# SmartSwitch_i2c.net
KiCad netlist of a schematic drawn in EAGLE
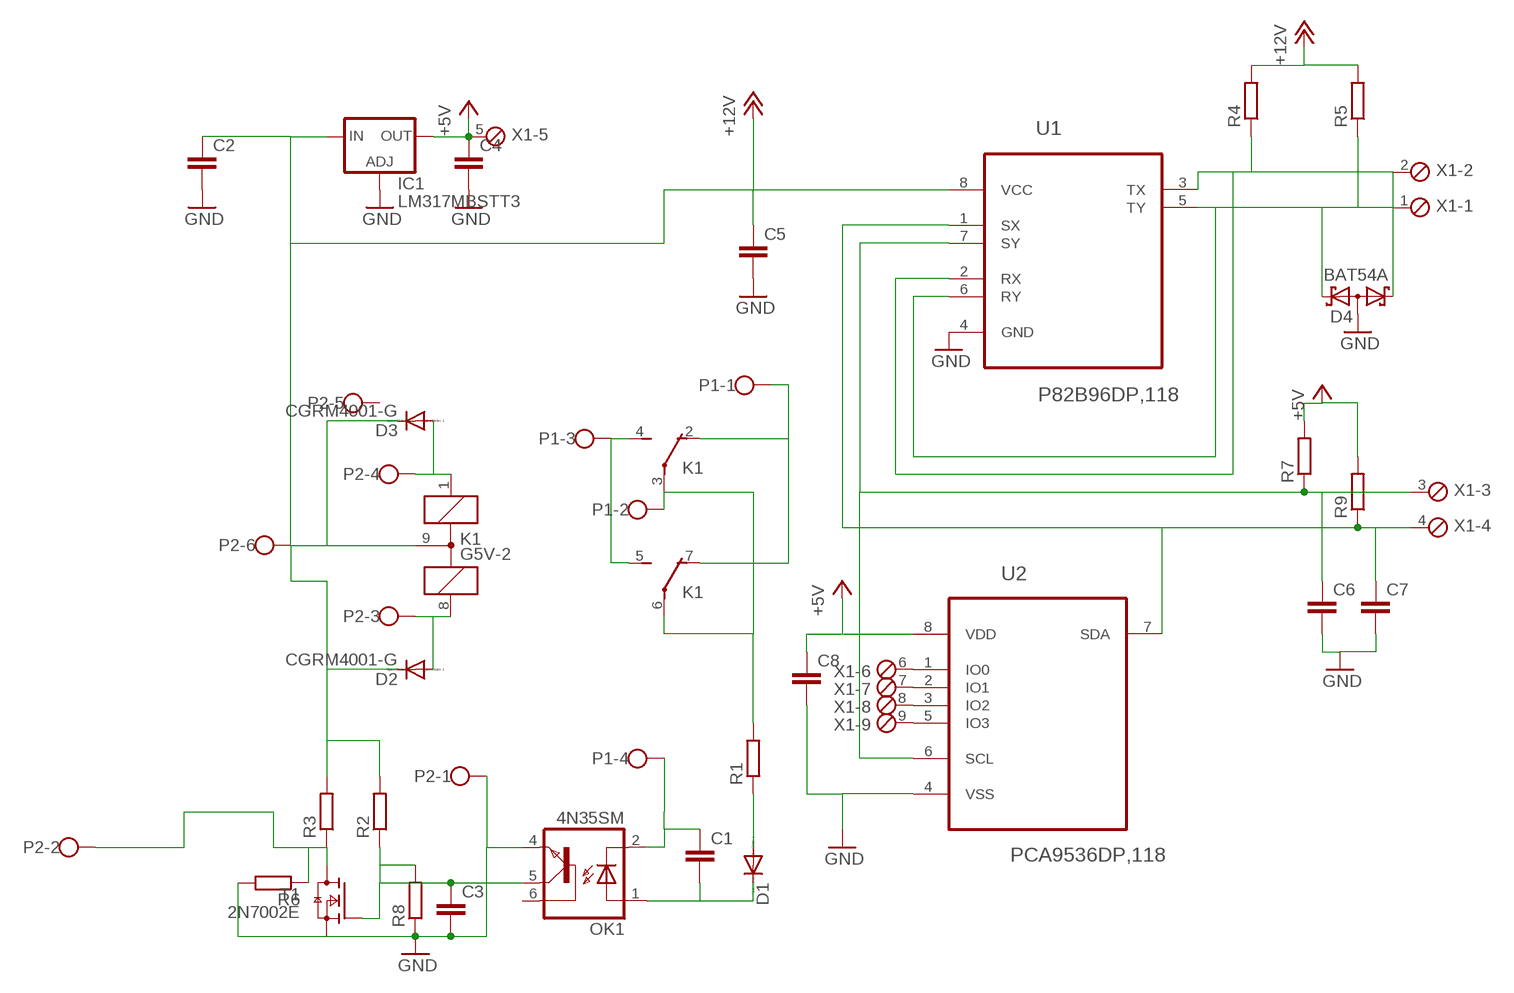
[diagram p0: schematic, sheet 1]

(export (version "E")
  (design (tool "Eeschema 10.0.6"))
  (components
    (comp (ref "C1")
      (value "C-EUC0805K")
      (footprint "eagle-import:C0805K")
      (libsource (lib "eagle-import") (part "resistor_C-EUC0805K"))
    )
    (comp (ref "C2")
      (value "C-EUC0805K")
      (footprint "eagle-import:C0805K")
      (libsource (lib "eagle-import") (part "resistor_C-EUC0805K"))
    )
    (comp (ref "C3")
      (value "C-EUC0805K")
      (footprint "eagle-import:C0805K")
      (libsource (lib "eagle-import") (part "resistor_C-EUC0805K"))
    )
    (comp (ref "C4")
      (value "C-EUC0805K")
      (footprint "eagle-import:C0805K")
      (libsource (lib "eagle-import") (part "resistor_C-EUC0805K"))
    )
    (comp (ref "C5")
      (value "C-EUC0603K")
      (footprint "eagle-import:C0603K")
      (libsource (lib "eagle-import") (part "C-EUC0603K"))
    )
    (comp (ref "C6")
      (value "C-EUC0402")
      (footprint "eagle-import:C0402")
      (libsource (lib "eagle-import") (part "C-EUC0402"))
    )
    (comp (ref "C7")
      (value "C-EUC0402")
      (footprint "eagle-import:C0402")
      (libsource (lib "eagle-import") (part "C-EUC0402"))
    )
    (comp (ref "C8")
      (value "C-EUC0603K")
      (footprint "eagle-import:C0603K")
      (libsource (lib "eagle-import") (part "C-EUC0603K"))
    )
    (comp (ref "D1")
      (value "DIODE-DO-214AC")
      (footprint "eagle-import:DO-214AC")
      (libsource (lib "eagle-import") (part "DIODE-DO-214AC"))
    )
    (comp (ref "D2")
      (value "CGRM4001-G")
      (footprint "eagle-import:SOD-123_MINI-SMA")
      (libsource (lib "eagle-import") (part "CGRM400-G1"))
    )
    (comp (ref "D3")
      (value "CGRM4001-G")
      (footprint "eagle-import:SOD-123_MINI-SMA")
      (libsource (lib "eagle-import") (part "CGRM400-G1"))
    )
    (comp (ref "D4")
      (value "BAT54A")
      (footprint "eagle-import:SOT23")
      (libsource (lib "eagle-import") (part "BAT54A"))
    )
    (comp (ref "IC1")
      (value "LM317MBSTT3")
      (footprint "eagle-import:SOT223")
      (libsource (lib "eagle-import") (part "LM317?MBSTT3"))
    )
    (comp (ref "K1")
      (value "G5V-2")
      (footprint "eagle-import:G5V-2")
      (fields (field (name "MPN") "G5V-2 5DC"))
      (libsource (lib "eagle-import") (part "G5V-2"))
    )
    (comp (ref "OK1")
      (value "4N35SM")
      (footprint "eagle-import:DIL6-SMD")
      (fields (field (name "MF") "FAIRCHILD SEMICONDUCTOR") (field (name "MPN") "4N35S-M"))
      (libsource (lib "eagle-import") (part "4N?MS35"))
    )
    (comp (ref "P1")
      (value "W237-4")
      (footprint "eagle-import:W237-4")
      (libsource (lib "eagle-import") (part "W237-4"))
    )
    (comp (ref "P2")
      (value "W237-6")
      (footprint "eagle-import:W237-6")
      (libsource (lib "eagle-import") (part "W237-6"))
    )
    (comp (ref "R1")
      (value "R-EU_R1206")
      (footprint "eagle-import:R1206")
      (libsource (lib "eagle-import") (part "resistor_R-EU_R1206"))
    )
    (comp (ref "R2")
      (value "R-EU_R0603")
      (footprint "eagle-import:R0603")
      (libsource (lib "eagle-import") (part "resistor_R-EU_R0603"))
    )
    (comp (ref "R3")
      (value "R-EU_R0603")
      (footprint "eagle-import:R0603")
      (libsource (lib "eagle-import") (part "resistor_R-EU_R0603"))
    )
    (comp (ref "R4")
      (value "R-EU_R1206")
      (footprint "eagle-import:R1206")
      (libsource (lib "eagle-import") (part "R-EU_R1206"))
    )
    (comp (ref "R5")
      (value "R-EU_R1206")
      (footprint "eagle-import:R1206")
      (libsource (lib "eagle-import") (part "R-EU_R1206"))
    )
    (comp (ref "R6")
      (value "R-EU_R0603")
      (footprint "eagle-import:R0603")
      (libsource (lib "eagle-import") (part "resistor_R-EU_R0603"))
    )
    (comp (ref "R7")
      (value "R-EU_R0603")
      (footprint "eagle-import:R0603")
      (libsource (lib "eagle-import") (part "R-EU_R0603"))
    )
    (comp (ref "R8")
      (value "R-EU_R0603")
      (footprint "eagle-import:R0603")
      (libsource (lib "eagle-import") (part "resistor_R-EU_R0603"))
    )
    (comp (ref "R9")
      (value "R-EU_R0603")
      (footprint "eagle-import:R0603")
      (libsource (lib "eagle-import") (part "R-EU_R0603"))
    )
    (comp (ref "T1")
      (value "2N7002E")
      (footprint "eagle-import:SOT23")
      (libsource (lib "eagle-import") (part "2N7002E"))
    )
    (comp (ref "U1")
      (value "P82B96DP,118")
      (footprint "eagle-import:SOP65P490X110-8N")
      (libsource (lib "eagle-import") (part "P82B96DP,118"))
    )
    (comp (ref "U2")
      (value "PCA9536DP,118")
      (footprint "eagle-import:SOP65P490X110-8N")
      (libsource (lib "eagle-import") (part "PCA9536DP,118"))
    )
    (comp (ref "X1")
      (value "MPT9")
      (footprint "eagle-import:9POL254")
      (libsource (lib "eagle-import") (part "MPT9"))
    )
  )
  (nets
    (net (code "1") (name "+5V") (class "Default")
      (node (ref "C4") (pin "1") (pinfunction "1_1") (pintype "passive"))
      (node (ref "C8") (pin "1") (pinfunction "1_1") (pintype "passive"))
      (node (ref "IC1") (pin "4") (pinfunction "OUT_4") (pintype "passive"))
      (node (ref "R7") (pin "2") (pinfunction "2_2") (pintype "passive"))
      (node (ref "R9") (pin "2") (pinfunction "2_2") (pintype "passive"))
      (node (ref "U2") (pin "8") (pinfunction "VDD_8") (pintype "power_in"))
      (node (ref "X1") (pin "5") (pinfunction "1_5") (pintype "passive"))
    )
    (net (code "2") (name "+12V") (class "Default")
      (node (ref "C2") (pin "1") (pinfunction "1_1") (pintype "passive"))
      (node (ref "C5") (pin "1") (pinfunction "1_1") (pintype "passive"))
      (node (ref "D2") (pin "C") (pinfunction "C_C") (pintype "passive"))
      (node (ref "D3") (pin "C") (pinfunction "C_C") (pintype "passive"))
      (node (ref "IC1") (pin "3") (pinfunction "IN_3") (pintype "input"))
      (node (ref "K1") (pin "9") (pinfunction "M_9") (pintype "passive"))
      (node (ref "P2") (pin "6") (pinfunction "KL_6") (pintype "passive"))
      (node (ref "R2") (pin "2") (pinfunction "2_2") (pintype "passive"))
      (node (ref "R3") (pin "2") (pinfunction "2_2") (pintype "passive"))
      (node (ref "R4") (pin "2") (pinfunction "2_2") (pintype "passive"))
      (node (ref "R5") (pin "2") (pinfunction "2_2") (pintype "passive"))
      (node (ref "U1") (pin "8") (pinfunction "VCC_8") (pintype "power_in"))
    )
    (net (code "3") (name "GND") (class "Default")
      (node (ref "C2") (pin "2") (pinfunction "2_2") (pintype "passive"))
      (node (ref "C3") (pin "2") (pinfunction "2_2") (pintype "passive"))
      (node (ref "C4") (pin "2") (pinfunction "2_2") (pintype "passive"))
      (node (ref "C5") (pin "2") (pinfunction "2_2") (pintype "passive"))
      (node (ref "C6") (pin "2") (pinfunction "2_2") (pintype "passive"))
      (node (ref "C7") (pin "2") (pinfunction "2_2") (pintype "passive"))
      (node (ref "C8") (pin "2") (pinfunction "2_2") (pintype "passive"))
      (node (ref "D4") (pin "3") (pinfunction "A1A2_3") (pintype "passive"))
      (node (ref "IC1") (pin "1") (pinfunction "ADJ_1") (pintype "input"))
      (node (ref "OK1") (pin "4") (pinfunction "EMI_4") (pintype "passive"))
      (node (ref "P2") (pin "1") (pinfunction "KL_1") (pintype "passive"))
      (node (ref "R6") (pin "2") (pinfunction "2_2") (pintype "passive"))
      (node (ref "R8") (pin "1") (pinfunction "1_1") (pintype "passive"))
      (node (ref "T1") (pin "2") (pinfunction "S_2") (pintype "passive"))
      (node (ref "U1") (pin "4") (pinfunction "GND_4") (pintype "passive"))
      (node (ref "U2") (pin "4") (pinfunction "VSS_4") (pintype "power_in"))
    )
    (net (code "4") (name "Net-(D1-PadA)") (class "Default")
      (node (ref "D1") (pin "A") (pinfunction "A_A") (pintype "passive"))
      (node (ref "R1") (pin "1") (pinfunction "1_1") (pintype "passive"))
    )
    (net (code "5") (name "Net-(D4-K1)") (class "Default")
      (node (ref "D4") (pin "1") (pinfunction "K1_1") (pintype "passive"))
      (node (ref "R4") (pin "1") (pinfunction "1_1") (pintype "passive"))
      (node (ref "U1") (pin "2") (pinfunction "RX_2") (pintype "input"))
      (node (ref "U1") (pin "3") (pinfunction "TX_3") (pintype "output"))
      (node (ref "X1") (pin "2") (pinfunction "1_2") (pintype "passive"))
    )
    (net (code "6") (name "Net-(D4-K2)") (class "Default")
      (node (ref "D4") (pin "2") (pinfunction "K2_2") (pintype "passive"))
      (node (ref "R5") (pin "1") (pinfunction "1_1") (pintype "passive"))
      (node (ref "U1") (pin "5") (pinfunction "TY_5") (pintype "output"))
      (node (ref "U1") (pin "6") (pinfunction "RY_6") (pintype "input"))
      (node (ref "X1") (pin "1") (pinfunction "1_1") (pintype "passive"))
    )
    (net (code "7") (name "Net-(K1A-2)") (class "Default")
      (node (ref "D2") (pin "A") (pinfunction "A_A") (pintype "passive"))
      (node (ref "K1") (pin "8") (pinfunction "2_8") (pintype "passive"))
      (node (ref "P2") (pin "3") (pinfunction "KL_3") (pintype "passive"))
    )
    (net (code "8") (name "Net-(K1B-O)") (class "Default")
      (node (ref "K1") (pin "2") (pinfunction "O_2") (pintype "passive"))
      (node (ref "K1") (pin "7") (pinfunction "O_7") (pintype "passive"))
      (node (ref "P1") (pin "1") (pinfunction "KL_1") (pintype "passive"))
    )
    (net (code "9") (name "Net-(K1B-P)") (class "Default")
      (node (ref "K1") (pin "3") (pinfunction "P_3") (pintype "passive"))
      (node (ref "K1") (pin "6") (pinfunction "P_6") (pintype "passive"))
      (node (ref "P1") (pin "2") (pinfunction "KL_2") (pintype "passive"))
      (node (ref "R1") (pin "2") (pinfunction "2_2") (pintype "passive"))
    )
    (net (code "10") (name "Net-(K1B-S)") (class "Default")
      (node (ref "K1") (pin "4") (pinfunction "S_4") (pintype "passive"))
      (node (ref "K1") (pin "5") (pinfunction "S_5") (pintype "passive"))
      (node (ref "P1") (pin "3") (pinfunction "KL_3") (pintype "passive"))
    )
    (net (code "11") (name "Net-(OK1-A)") (class "Default")
      (node (ref "C1") (pin "2") (pinfunction "2_2") (pintype "passive"))
      (node (ref "D1") (pin "C") (pinfunction "C_C") (pintype "passive"))
      (node (ref "OK1") (pin "1") (pinfunction "A_1") (pintype "passive"))
    )
    (net (code "12") (name "Net-(OK1-C)") (class "Default")
      (node (ref "C1") (pin "1") (pinfunction "1_1") (pintype "passive"))
      (node (ref "OK1") (pin "2") (pinfunction "C_2") (pintype "passive"))
      (node (ref "P1") (pin "4") (pinfunction "KL_4") (pintype "passive"))
    )
    (net (code "13") (name "Net-(OK1-COL)") (class "Default")
      (node (ref "C3") (pin "1") (pinfunction "1_1") (pintype "passive"))
      (node (ref "OK1") (pin "5") (pinfunction "COL_5") (pintype "passive"))
      (node (ref "R2") (pin "1") (pinfunction "1_1") (pintype "passive"))
      (node (ref "R8") (pin "2") (pinfunction "2_2") (pintype "passive"))
      (node (ref "T1") (pin "1") (pinfunction "G_1") (pintype "passive"))
    )
    (net (code "14") (name "Net-(P2B-KL)") (class "Default")
      (node (ref "P2") (pin "2") (pinfunction "KL_2") (pintype "passive"))
      (node (ref "R3") (pin "1") (pinfunction "1_1") (pintype "passive"))
      (node (ref "R6") (pin "1") (pinfunction "1_1") (pintype "passive"))
      (node (ref "T1") (pin "3") (pinfunction "D_3") (pintype "passive"))
    )
    (net (code "15") (name "Net-(P2D-KL)") (class "Default")
      (node (ref "D3") (pin "A") (pinfunction "A_A") (pintype "passive"))
      (node (ref "K1") (pin "1") (pinfunction "1_1") (pintype "passive"))
      (node (ref "P2") (pin "4") (pinfunction "KL_4") (pintype "passive"))
    )
    (net (code "16") (name "Net-(U1-SX)") (class "Default")
      (node (ref "C7") (pin "1") (pinfunction "1_1") (pintype "passive"))
      (node (ref "R9") (pin "1") (pinfunction "1_1") (pintype "passive"))
      (node (ref "U1") (pin "1") (pinfunction "SX_1") (pintype "bidirectional"))
      (node (ref "U2") (pin "7") (pinfunction "SDA_7") (pintype "bidirectional"))
      (node (ref "X1") (pin "4") (pinfunction "1_4") (pintype "passive"))
    )
    (net (code "17") (name "Net-(U1-SY)") (class "Default")
      (node (ref "C6") (pin "1") (pinfunction "1_1") (pintype "passive"))
      (node (ref "R7") (pin "1") (pinfunction "1_1") (pintype "passive"))
      (node (ref "U1") (pin "7") (pinfunction "SY_7") (pintype "bidirectional"))
      (node (ref "U2") (pin "6") (pinfunction "SCL_6") (pintype "input"))
      (node (ref "X1") (pin "3") (pinfunction "1_3") (pintype "passive"))
    )
    (net (code "18") (name "Net-(U2-IO0)") (class "Default")
      (node (ref "U2") (pin "1") (pinfunction "IO0_1") (pintype "bidirectional"))
      (node (ref "X1") (pin "6") (pinfunction "1_6") (pintype "passive"))
    )
    (net (code "19") (name "Net-(U2-IO1)") (class "Default")
      (node (ref "U2") (pin "2") (pinfunction "IO1_2") (pintype "bidirectional"))
      (node (ref "X1") (pin "7") (pinfunction "1_7") (pintype "passive"))
    )
    (net (code "20") (name "Net-(U2-IO2)") (class "Default")
      (node (ref "U2") (pin "3") (pinfunction "IO2_3") (pintype "bidirectional"))
      (node (ref "X1") (pin "8") (pinfunction "1_8") (pintype "passive"))
    )
    (net (code "21") (name "Net-(U2-IO3)") (class "Default")
      (node (ref "U2") (pin "5") (pinfunction "IO3_5") (pintype "bidirectional"))
      (node (ref "X1") (pin "9") (pinfunction "1_9") (pintype "passive"))
    )
    (net (code "22") (name "unconnected-(OK1-BAS-Pad6)") (class "Default")
      (node (ref "OK1") (pin "6") (pinfunction "BAS_6") (pintype "passive"))
    )
    (net (code "23") (name "unconnected-(P2E-KL-Pad5)") (class "Default")
      (node (ref "P2") (pin "5") (pinfunction "KL_5") (pintype "passive"))
    )
  )
)
